# CD_Air_Detector_V2_0.net
KiCad netlist of a schematic drawn in EasyEDA Pro
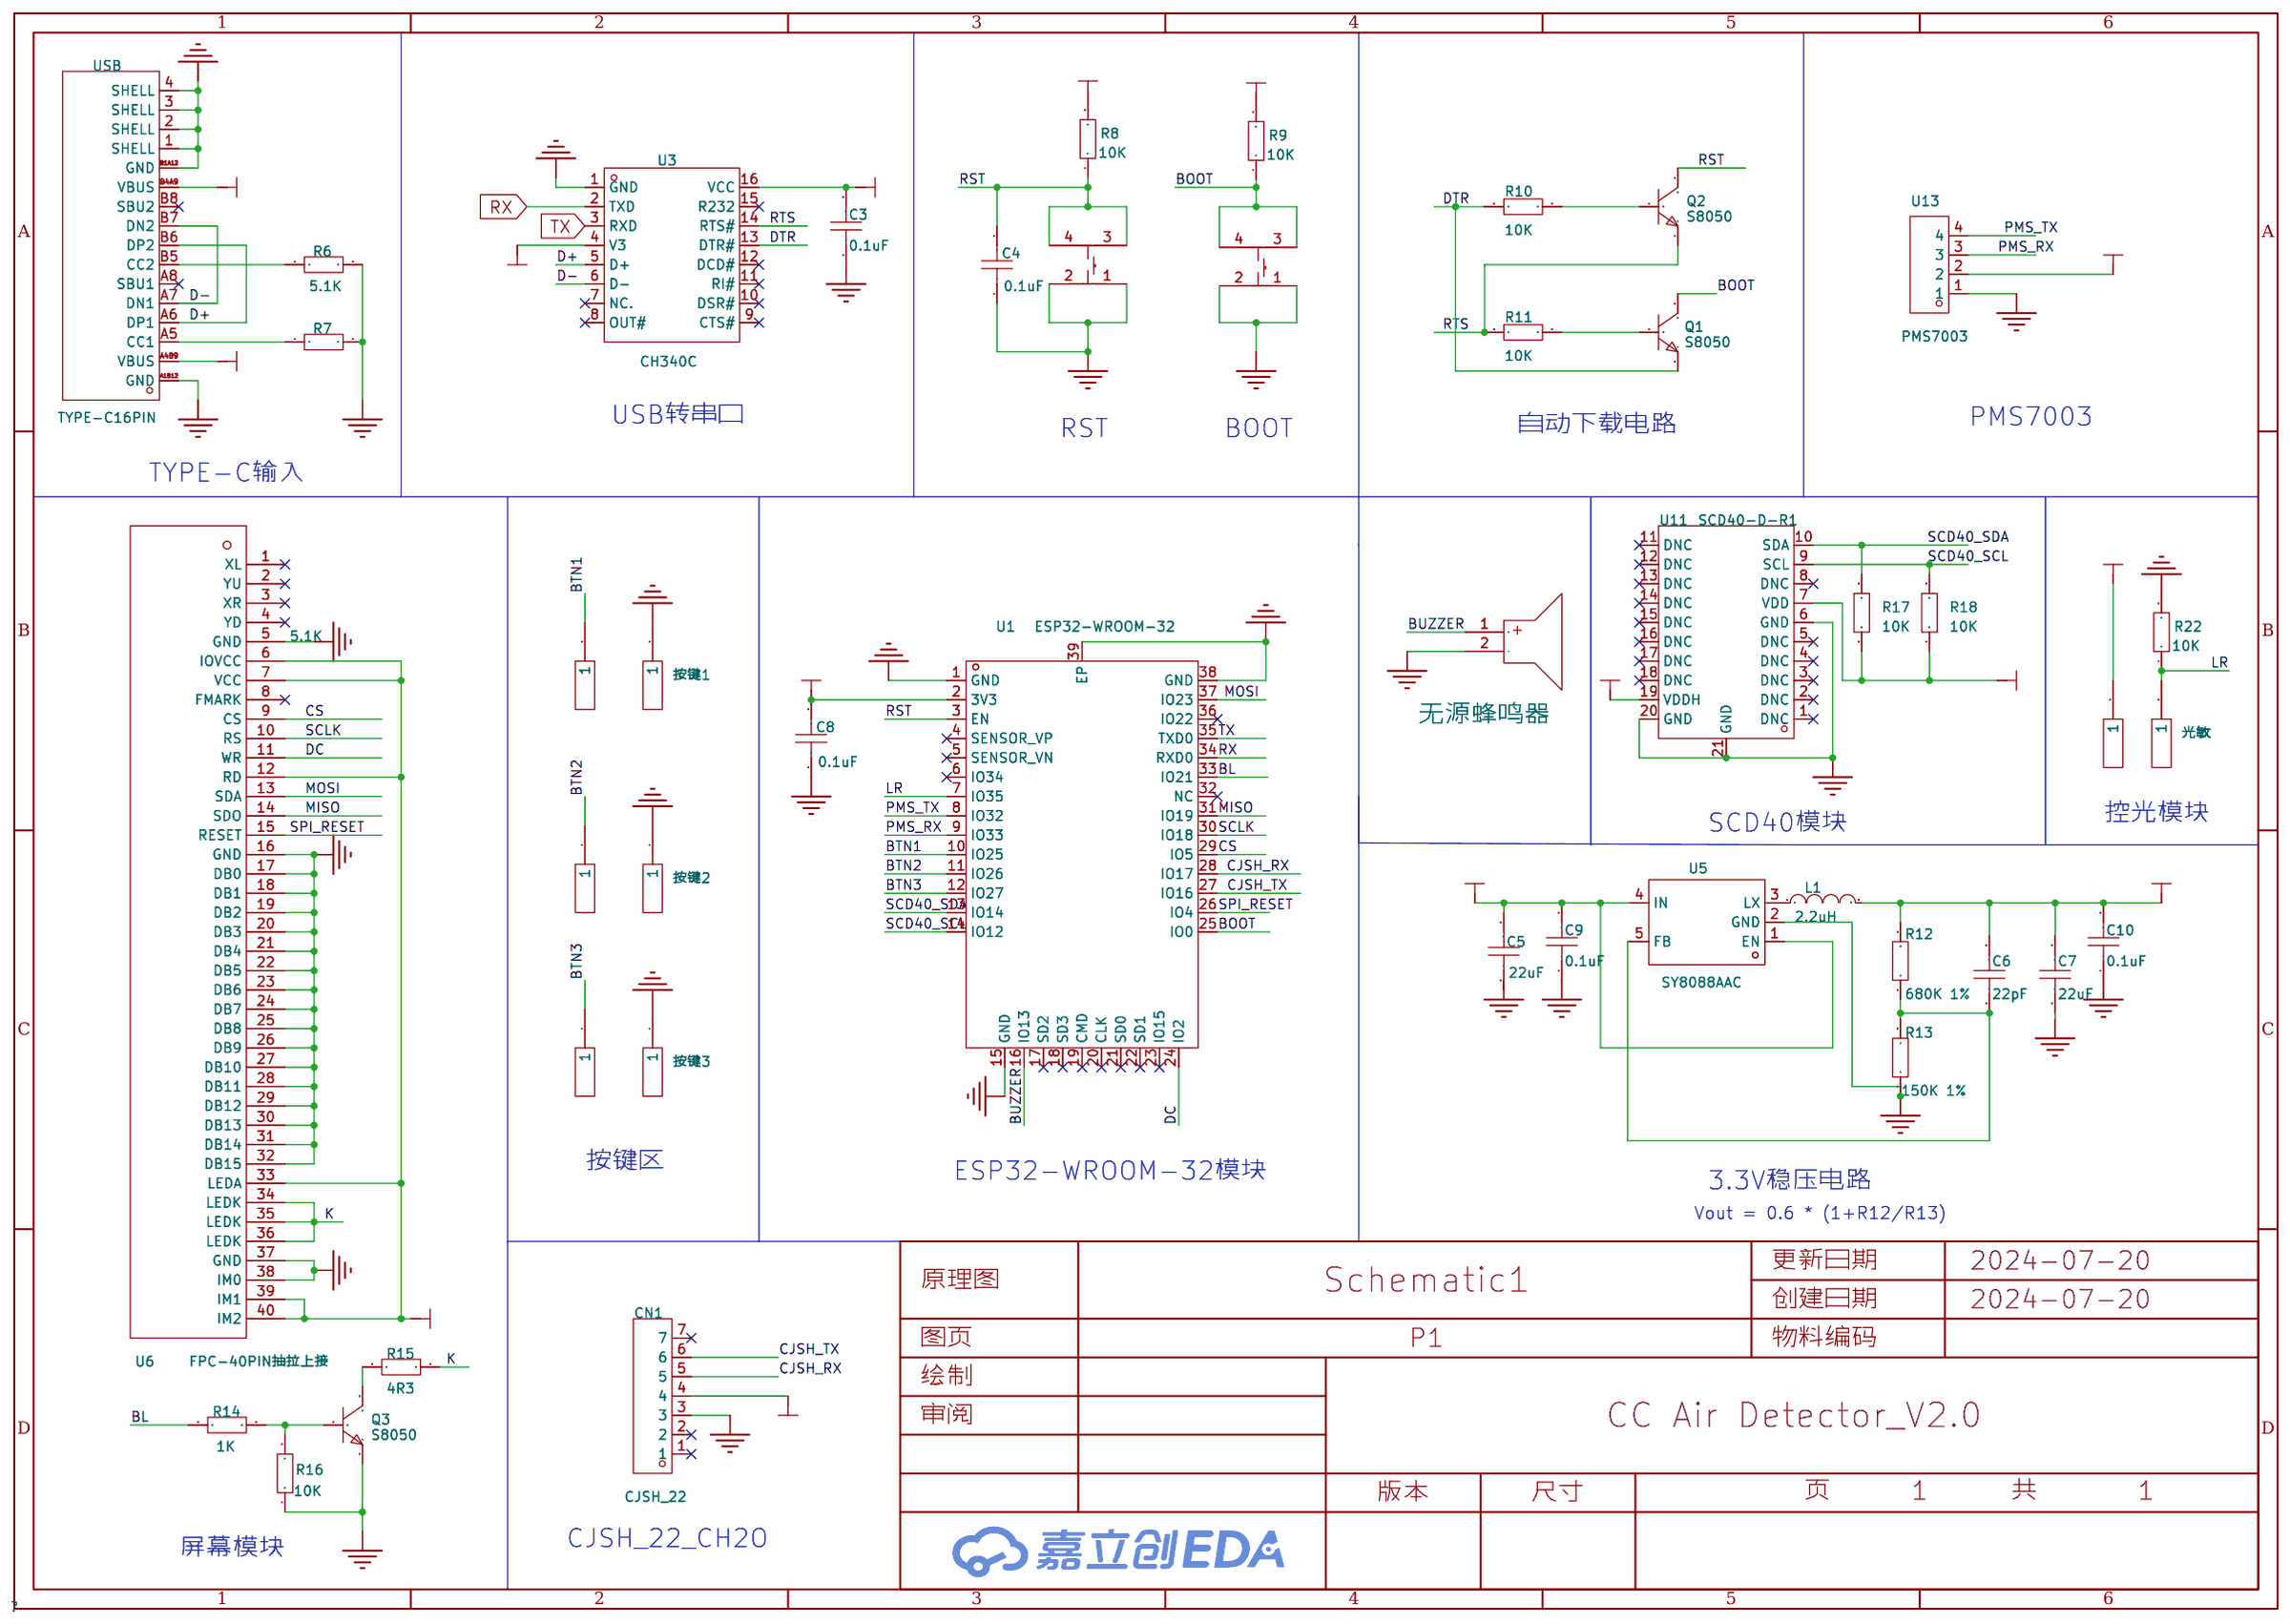
[diagram p0: schematic sheet]

(export (version "E")
  (design (tool "Eeschema 10.0.6"))
  (components
    (comp (ref "C3")
      (value "0.1uF")
      (footprint "easyedapro:C0603")
      (libsource (lib "easyedapro") (part "CapAcitance"))
    )
    (comp (ref "C4")
      (value "0.1uF")
      (footprint "easyedapro:C0603")
      (libsource (lib "easyedapro") (part "CapAcitance"))
    )
    (comp (ref "C5")
      (value "22uF")
      (footprint "easyedapro:C0603")
      (libsource (lib "easyedapro") (part "CapAcitance"))
    )
    (comp (ref "C6")
      (value "22pF")
      (footprint "easyedapro:C0603")
      (libsource (lib "easyedapro") (part "CapAcitance"))
    )
    (comp (ref "C7")
      (value "22uF")
      (footprint "easyedapro:C0603")
      (libsource (lib "easyedapro") (part "CapAcitance"))
    )
    (comp (ref "C8")
      (value "0.1uF")
      (footprint "easyedapro:C0603")
      (libsource (lib "easyedapro") (part "CapAcitance"))
    )
    (comp (ref "C9")
      (value "0.1uF")
      (footprint "easyedapro:C0603")
      (libsource (lib "easyedapro") (part "CapAcitance"))
    )
    (comp (ref "C10")
      (value "0.1uF")
      (footprint "easyedapro:C0603")
      (libsource (lib "easyedapro") (part "CapAcitance"))
    )
    (comp (ref "CN1")
      (value "CJSH_22")
      (footprint "easyedapro:CONN-TH_1.25T-7P-DP")
      (description "插针结构:1x7P;间距:1.25mm;安装方式:直插;参考系列:-;总PIN数:7P;排数:1;每排PIN数:7;行距:-;额定电流:1A;工作温度范围:-25°C~+85°C;")
      (fields (field (name "Manufacturer") "韩国韩荣"))
      (libsource (lib "easyedapro") (part "1.25T-7P-DP"))
    )
    (comp (ref "L1")
      (value "2.2uH")
      (footprint "easyedapro:L0805")
      (libsource (lib "easyedapro") (part "SDFL2012S100KTF"))
    )
    (comp (ref "Q1")
      (value "S8050")
      (footprint "easyedapro:SOT-23-3_L2.9-W1.3-P1.90-LS2.4-BR")
      (description "NPN 25V 500mA 120-400 SOT-23")
      (fields (field (name "Manufacturer") "Doeshare(德芯)"))
      (libsource (lib "easyedapro") (part "S8050_C2931719"))
    )
    (comp (ref "Q2")
      (value "S8050")
      (footprint "easyedapro:SOT-23-3_L2.9-W1.3-P1.90-LS2.4-BR")
      (description "NPN 25V 500mA 120-400 SOT-23")
      (fields (field (name "Manufacturer") "Doeshare(德芯)"))
      (libsource (lib "easyedapro") (part "S8050_C2931719"))
    )
    (comp (ref "Q3")
      (value "S8050")
      (footprint "easyedapro:SOT-23-3_L2.9-W1.3-P1.90-LS2.4-BR")
      (description "NPN 25V 500mA 120-400 SOT-23")
      (fields (field (name "Manufacturer") "Doeshare(德芯)"))
      (libsource (lib "easyedapro") (part "S8050_C2931719"))
    )
    (comp (ref "R6") (value "5.1K") (footprint "easyedapro:R0603") (libsource (lib "easyedapro") (part "电阻")))
    (comp (ref "R7") (value "5.1K") (footprint "easyedapro:R0603") (libsource (lib "easyedapro") (part "电阻")))
    (comp (ref "R8") (value "10K") (footprint "easyedapro:R0603") (libsource (lib "easyedapro") (part "电阻")))
    (comp (ref "R9") (value "10K") (footprint "easyedapro:R0603") (libsource (lib "easyedapro") (part "电阻")))
    (comp (ref "R10") (value "10K") (footprint "easyedapro:R0603") (libsource (lib "easyedapro") (part "电阻")))
    (comp (ref "R11") (value "10K") (footprint "easyedapro:R0603") (libsource (lib "easyedapro") (part "电阻")))
    (comp (ref "R12")
      (value "680K 1%")
      (footprint "easyedapro:R0603")
      (libsource (lib "easyedapro") (part "电阻"))
    )
    (comp (ref "R13")
      (value "150K 1%")
      (footprint "easyedapro:R0603")
      (libsource (lib "easyedapro") (part "电阻"))
    )
    (comp (ref "R14") (value "1K") (footprint "easyedapro:R0603") (libsource (lib "easyedapro") (part "电阻")))
    (comp (ref "R15") (value "4R3") (footprint "easyedapro:R0603") (libsource (lib "easyedapro") (part "电阻")))
    (comp (ref "R16") (value "10K") (footprint "easyedapro:R0603") (libsource (lib "easyedapro") (part "电阻")))
    (comp (ref "R17") (value "10K") (footprint "easyedapro:R0603") (libsource (lib "easyedapro") (part "电阻")))
    (comp (ref "R18") (value "10K") (footprint "easyedapro:R0603") (libsource (lib "easyedapro") (part "电阻")))
    (comp (ref "R22") (value "10K") (footprint "easyedapro:R0603") (libsource (lib "easyedapro") (part "电阻")))
    (comp (ref "U1")
      (value "ESP32-WROOM-32")
      (footprint "easyedapro:WIFIM-SMD_ESP-WROOM-32")
      (description "WiFi+双模蓝牙 双核CPU 网口 顶配MCU 低功耗蓝牙 ESP32系列ESP-WROOM-32模组/ESP-32S 4MB")
      (fields (field (name "Manufacturer") "ESPRESSIF(乐鑫)"))
      (libsource (lib "easyedapro") (part "ESP-WROOM-32"))
    )
    (comp (ref "U2")
      (value "贴片按键(轻触开关)")
      (footprint "easyedapro:SW-SMD_4P-L4.2-W3.2-P2.15-LS4.6")
      (libsource (lib "easyedapro") (part "贴片按键(轻触开关)"))
    )
    (comp (ref "U3")
      (value "CH340C")
      (footprint "easyedapro:SOP-16_L10.0-W3.9-P1.27-LS6.0-BL")
      (description "应用功能:收发器;接口协议:USB 2.0;数据速率:2Mbps;")
      (fields (field (name "Manufacturer") "WCH(南京沁恒)"))
      (libsource (lib "easyedapro") (part "CH340C"))
    )
    (comp (ref "U4")
      (value "贴片按键(轻触开关)")
      (footprint "easyedapro:SW-SMD_4P-L4.2-W3.2-P2.15-LS4.6")
      (libsource (lib "easyedapro") (part "贴片按键(轻触开关)"))
    )
    (comp (ref "U5")
      (value "SY8088AAC")
      (footprint "easyedapro:SOT-23-5_L3.0-W1.7-P0.95-LS2.8-BR")
      (description "功能类型:降压型;输入电压:-;输出电流(最大值):-;")
      (fields (field (name "Manufacturer") "silergy(矽力杰)"))
      (libsource (lib "easyedapro") (part "SY8088AAC"))
    )
    (comp (ref "U6")
      (value "FPC-40PIN抽拉上接")
      (footprint "easyedapro:FPC_40PIN")
      (libsource (lib "easyedapro") (part "FPC_连接器_40PIN"))
    )
    (comp (ref "U8")
      (value "~")
      (footprint "easyedapro:长圆形单面焊盘")
      (libsource (lib "easyedapro") (part "长圆形单面焊盘"))
    )
    (comp (ref "U9")
      (value "~")
      (footprint "easyedapro:长圆形单面焊盘")
      (libsource (lib "easyedapro") (part "长圆形单面焊盘"))
    )
    (comp (ref "U10")
      (value "~")
      (footprint "easyedapro:长圆形单面焊盘")
      (libsource (lib "easyedapro") (part "长圆形单面焊盘"))
    )
    (comp (ref "U11")
      (value "SCD40-D-R1")
      (footprint "easyedapro:LGA-20_L10.1-W10.1-P1.25-TL")
      (description "气体类型:空气质量;精度:±5%;")
      (fields (field (name "Manufacturer") "Sensirion(瑞士盛思锐)"))
      (libsource (lib "easyedapro") (part "SCD40-D-R1"))
    )
    (comp (ref "U12")
      (value "~")
      (footprint "easyedapro:长圆形单面焊盘")
      (libsource (lib "easyedapro") (part "长圆形单面焊盘"))
    )
    (comp (ref "U13")
      (value "PMS7003")
      (footprint "easyedapro:CONN-TH_4P-P2.50-XH2.54-4P")
      (libsource (lib "easyedapro") (part "XH2.54-4P(直针)"))
    )
    (comp (ref "USB")
      (value "TYPE-C16PIN")
      (footprint "easyedapro:USB-C-SMD_TYPE-C16PIN")
      (description "连接器类型:Type-C;标准:-;公母:母;端口数量:1;触点数量:16P;安装方式:卧贴;额定电流 - 电源:3A;工作温度范围:-40°C~+85°C;")
      (fields (field (name "Manufacturer") "SHOU HAN(首韩)"))
      (libsource (lib "easyedapro") (part "TYPE-C16PIN"))
    )
    (comp (ref "光敏")
      (value "~")
      (footprint "easyedapro:长圆形单面焊盘")
      (libsource (lib "easyedapro") (part "长圆形单面焊盘"))
    )
    (comp (ref "按键1")
      (value "~")
      (footprint "easyedapro:长圆形单面焊盘")
      (libsource (lib "easyedapro") (part "长圆形单面焊盘"))
    )
    (comp (ref "按键2")
      (value "~")
      (footprint "easyedapro:长圆形单面焊盘")
      (libsource (lib "easyedapro") (part "长圆形单面焊盘"))
    )
    (comp (ref "按键3")
      (value "~")
      (footprint "easyedapro:长圆形单面焊盘")
      (libsource (lib "easyedapro") (part "长圆形单面焊盘"))
    )
    (comp (ref "无源蜂鸣器")
      (value "无源蜂鸣器")
      (footprint "easyedapro:BUZ-TH_BD12.0-P6.50-D0.6-FD")
      (fields (field (name "Manufacturer") "Fengming(锋鸣电子)"))
      (libsource (lib "easyedapro") (part "YS-MBZ12095C05R42K4000"))
    )
  )
  (nets
    (net (code "1") (name "/BL") (class "Default")
      (node (ref "R14") (pin "1") (pinfunction "1_1") (pintype "input"))
      (node (ref "U1") (pin "33") (pinfunction "IO21_33") (pintype "unspecified"))
    )
    (net (code "2") (name "/BOOT") (class "Default")
      (node (ref "Q1") (pin "3") (pinfunction "C_3") (pintype "input"))
      (node (ref "R9") (pin "1") (pinfunction "1_1") (pintype "input"))
      (node (ref "U1") (pin "25") (pinfunction "IO0_25") (pintype "unspecified"))
      (node (ref "U4") (pin "3") (pinfunction "3_3") (pintype "unspecified"))
      (node (ref "U4") (pin "4") (pinfunction "4_4") (pintype "unspecified"))
    )
    (net (code "3") (name "/BTN1") (class "Default")
      (node (ref "U1") (pin "10") (pinfunction "IO25_10") (pintype "unspecified"))
      (node (ref "U8") (pin "1") (pinfunction "1_1") (pintype "input"))
    )
    (net (code "4") (name "/BTN2") (class "Default")
      (node (ref "U1") (pin "11") (pinfunction "IO26_11") (pintype "unspecified"))
      (node (ref "U9") (pin "1") (pinfunction "1_1") (pintype "input"))
    )
    (net (code "5") (name "/BTN3") (class "Default")
      (node (ref "U1") (pin "12") (pinfunction "IO27_12") (pintype "unspecified"))
      (node (ref "U10") (pin "1") (pinfunction "1_1") (pintype "input"))
    )
    (net (code "6") (name "/BUZZER") (class "Default")
      (node (ref "U1") (pin "16") (pinfunction "IO13_16") (pintype "unspecified"))
      (node (ref "无源蜂鸣器") (pin "1") (pinfunction "+_1") (pintype "input"))
    )
    (net (code "7") (name "/CJSH_RX") (class "Default")
      (node (ref "CN1") (pin "5") (pinfunction "5_5") (pintype "unspecified"))
      (node (ref "U1") (pin "28") (pinfunction "IO17_28") (pintype "unspecified"))
    )
    (net (code "8") (name "/CJSH_TX") (class "Default")
      (node (ref "CN1") (pin "6") (pinfunction "6_6") (pintype "unspecified"))
      (node (ref "U1") (pin "27") (pinfunction "IO16_27") (pintype "unspecified"))
    )
    (net (code "9") (name "/CS") (class "Default")
      (node (ref "U1") (pin "29") (pinfunction "IO5_29") (pintype "unspecified"))
      (node (ref "U6") (pin "9") (pinfunction "CS_9") (pintype "input"))
    )
    (net (code "10") (name "/D+") (class "Default")
      (node (ref "U3") (pin "5") (pinfunction "D+_5") (pintype "unspecified"))
      (node (ref "USB") (pin "A6") (pinfunction "DP1_A6") (pintype "unspecified"))
      (node (ref "USB") (pin "B6") (pinfunction "DP2_B6") (pintype "unspecified"))
    )
    (net (code "11") (name "/D-") (class "Default")
      (node (ref "U3") (pin "6") (pinfunction "D-_6") (pintype "unspecified"))
      (node (ref "USB") (pin "A7") (pinfunction "DN1_A7") (pintype "unspecified"))
      (node (ref "USB") (pin "B7") (pinfunction "DN2_B7") (pintype "unspecified"))
    )
    (net (code "12") (name "/DC") (class "Default")
      (node (ref "U1") (pin "24") (pinfunction "IO2_24") (pintype "unspecified"))
      (node (ref "U6") (pin "11") (pinfunction "WR_11") (pintype "input"))
    )
    (net (code "13") (name "/DTR") (class "Default")
      (node (ref "Q1") (pin "2") (pinfunction "E_2") (pintype "input"))
      (node (ref "R10") (pin "1") (pinfunction "1_1") (pintype "input"))
      (node (ref "U3") (pin "13") (pinfunction "DTR#_13") (pintype "unspecified"))
    )
    (net (code "14") (name "/K") (class "Default")
      (node (ref "R15") (pin "2") (pinfunction "2_2") (pintype "input"))
      (node (ref "U6") (pin "34") (pinfunction "LEDK_34") (pintype "input"))
      (node (ref "U6") (pin "35") (pinfunction "LEDK_35") (pintype "input"))
      (node (ref "U6") (pin "36") (pinfunction "LEDK_36") (pintype "input"))
    )
    (net (code "15") (name "/LR") (class "Default")
      (node (ref "R22") (pin "1") (pinfunction "1_1") (pintype "input"))
      (node (ref "U1") (pin "7") (pinfunction "IO35_7") (pintype "unspecified"))
      (node (ref "光敏") (pin "1") (pinfunction "1_1") (pintype "input"))
    )
    (net (code "16") (name "/MISO") (class "Default")
      (node (ref "U1") (pin "31") (pinfunction "IO19_31") (pintype "unspecified"))
      (node (ref "U6") (pin "14") (pinfunction "SDO_14") (pintype "input"))
    )
    (net (code "17") (name "/MOSI") (class "Default")
      (node (ref "U1") (pin "37") (pinfunction "IO23_37") (pintype "unspecified"))
      (node (ref "U6") (pin "13") (pinfunction "SDA_13") (pintype "input"))
    )
    (net (code "18") (name "/PMS_RX") (class "Default")
      (node (ref "U1") (pin "9") (pinfunction "IO33_9") (pintype "unspecified"))
      (node (ref "U13") (pin "3") (pinfunction "3_3") (pintype "unspecified"))
    )
    (net (code "19") (name "/PMS_TX") (class "Default")
      (node (ref "U1") (pin "8") (pinfunction "IO32_8") (pintype "unspecified"))
      (node (ref "U13") (pin "4") (pinfunction "4_4") (pintype "unspecified"))
    )
    (net (code "20") (name "/RST") (class "Default")
      (node (ref "C4") (pin "2") (pinfunction "2_2") (pintype "input"))
      (node (ref "Q2") (pin "3") (pinfunction "C_3") (pintype "input"))
      (node (ref "R8") (pin "1") (pinfunction "1_1") (pintype "input"))
      (node (ref "U1") (pin "3") (pinfunction "EN_3") (pintype "unspecified"))
      (node (ref "U2") (pin "3") (pinfunction "3_3") (pintype "unspecified"))
      (node (ref "U2") (pin "4") (pinfunction "4_4") (pintype "unspecified"))
    )
    (net (code "21") (name "/RTS") (class "Default")
      (node (ref "Q2") (pin "2") (pinfunction "E_2") (pintype "input"))
      (node (ref "R11") (pin "1") (pinfunction "1_1") (pintype "input"))
      (node (ref "U3") (pin "14") (pinfunction "RTS#_14") (pintype "unspecified"))
    )
    (net (code "22") (name "/SCD40_SCL") (class "Default")
      (node (ref "R18") (pin "2") (pinfunction "2_2") (pintype "input"))
      (node (ref "U1") (pin "14") (pinfunction "IO12_14") (pintype "unspecified"))
      (node (ref "U11") (pin "9") (pinfunction "SCL_9") (pintype "unspecified"))
    )
    (net (code "23") (name "/SCD40_SDA") (class "Default")
      (node (ref "R17") (pin "2") (pinfunction "2_2") (pintype "input"))
      (node (ref "U1") (pin "13") (pinfunction "IO14_13") (pintype "unspecified"))
      (node (ref "U11") (pin "10") (pinfunction "SDA_10") (pintype "unspecified"))
    )
    (net (code "24") (name "/SCLK") (class "Default")
      (node (ref "U1") (pin "30") (pinfunction "IO18_30") (pintype "unspecified"))
      (node (ref "U6") (pin "10") (pinfunction "RS_10") (pintype "input"))
    )
    (net (code "25") (name "/SPI_RESET") (class "Default")
      (node (ref "U1") (pin "26") (pinfunction "IO4_26") (pintype "unspecified"))
      (node (ref "U6") (pin "15") (pinfunction "RESET_15") (pintype "input"))
    )
    (net (code "26") (name "3V3") (class "Default")
      (node (ref "C10") (pin "2") (pinfunction "2_2") (pintype "input"))
      (node (ref "C3") (pin "2") (pinfunction "2_2") (pintype "input"))
      (node (ref "C6") (pin "2") (pinfunction "2_2") (pintype "input"))
      (node (ref "C7") (pin "2") (pinfunction "2_2") (pintype "input"))
      (node (ref "C8") (pin "2") (pinfunction "2_2") (pintype "input"))
      (node (ref "L1") (pin "2") (pinfunction "2_2") (pintype "unspecified"))
      (node (ref "R12") (pin "2") (pinfunction "2_2") (pintype "input"))
      (node (ref "R17") (pin "1") (pinfunction "1_1") (pintype "input"))
      (node (ref "R18") (pin "1") (pinfunction "1_1") (pintype "input"))
      (node (ref "R8") (pin "2") (pinfunction "2_2") (pintype "input"))
      (node (ref "R9") (pin "2") (pinfunction "2_2") (pintype "input"))
      (node (ref "U1") (pin "2") (pinfunction "3V3_2") (pintype "unspecified"))
      (node (ref "U11") (pin "19") (pinfunction "VDDH_19") (pintype "unspecified"))
      (node (ref "U11") (pin "7") (pinfunction "VDD_7") (pintype "unspecified"))
      (node (ref "U12") (pin "1") (pinfunction "1_1") (pintype "input"))
      (node (ref "U3") (pin "16") (pinfunction "VCC_16") (pintype "unspecified"))
      (node (ref "U3") (pin "4") (pinfunction "V3_4") (pintype "unspecified"))
      (node (ref "U6") (pin "12") (pinfunction "RD_12") (pintype "input"))
      (node (ref "U6") (pin "33") (pinfunction "LEDA_33") (pintype "input"))
      (node (ref "U6") (pin "39") (pinfunction "IM1_39") (pintype "input"))
      (node (ref "U6") (pin "40") (pinfunction "IM2_40") (pintype "input"))
      (node (ref "U6") (pin "6") (pinfunction "IOVCC_6") (pintype "input"))
      (node (ref "U6") (pin "7") (pinfunction "VCC_7") (pintype "input"))
    )
    (net (code "27") (name "GND") (class "Default")
      (node (ref "C10") (pin "1") (pinfunction "1_1") (pintype "input"))
      (node (ref "C3") (pin "1") (pinfunction "1_1") (pintype "input"))
      (node (ref "C4") (pin "1") (pinfunction "1_1") (pintype "input"))
      (node (ref "C5") (pin "1") (pinfunction "1_1") (pintype "input"))
      (node (ref "C7") (pin "1") (pinfunction "1_1") (pintype "input"))
      (node (ref "C8") (pin "1") (pinfunction "1_1") (pintype "input"))
      (node (ref "C9") (pin "1") (pinfunction "1_1") (pintype "input"))
      (node (ref "CN1") (pin "3") (pinfunction "3_3") (pintype "unspecified"))
      (node (ref "Q3") (pin "2") (pinfunction "E_2") (pintype "input"))
      (node (ref "R13") (pin "1") (pinfunction "1_1") (pintype "input"))
      (node (ref "R16") (pin "1") (pinfunction "1_1") (pintype "input"))
      (node (ref "R22") (pin "2") (pinfunction "2_2") (pintype "input"))
      (node (ref "R6") (pin "2") (pinfunction "2_2") (pintype "input"))
      (node (ref "R7") (pin "2") (pinfunction "2_2") (pintype "input"))
      (node (ref "U1") (pin "1") (pinfunction "GND_1") (pintype "unspecified"))
      (node (ref "U1") (pin "15") (pinfunction "GND_15") (pintype "unspecified"))
      (node (ref "U1") (pin "38") (pinfunction "GND_38") (pintype "unspecified"))
      (node (ref "U1") (pin "39") (pinfunction "EP_39") (pintype "unspecified"))
      (node (ref "U11") (pin "20") (pinfunction "GND_20") (pintype "unspecified"))
      (node (ref "U11") (pin "21") (pinfunction "GND_21") (pintype "unspecified"))
      (node (ref "U11") (pin "6") (pinfunction "GND_6") (pintype "unspecified"))
      (node (ref "U13") (pin "1") (pinfunction "1_1") (pintype "unspecified"))
      (node (ref "U2") (pin "1") (pinfunction "1_1") (pintype "unspecified"))
      (node (ref "U2") (pin "2") (pinfunction "2_2") (pintype "unspecified"))
      (node (ref "U3") (pin "1") (pinfunction "GND_1") (pintype "unspecified"))
      (node (ref "U4") (pin "1") (pinfunction "1_1") (pintype "unspecified"))
      (node (ref "U4") (pin "2") (pinfunction "2_2") (pintype "unspecified"))
      (node (ref "U5") (pin "2") (pinfunction "GND_2") (pintype "input"))
      (node (ref "U6") (pin "16") (pinfunction "GND_16") (pintype "input"))
      (node (ref "U6") (pin "17") (pinfunction "DB0_17") (pintype "input"))
      (node (ref "U6") (pin "18") (pinfunction "DB1_18") (pintype "input"))
      (node (ref "U6") (pin "19") (pinfunction "DB2_19") (pintype "input"))
      (node (ref "U6") (pin "20") (pinfunction "DB3_20") (pintype "input"))
      (node (ref "U6") (pin "21") (pinfunction "DB4_21") (pintype "input"))
      (node (ref "U6") (pin "22") (pinfunction "DB5_22") (pintype "input"))
      (node (ref "U6") (pin "23") (pinfunction "DB6_23") (pintype "input"))
      (node (ref "U6") (pin "24") (pinfunction "DB7_24") (pintype "input"))
      (node (ref "U6") (pin "25") (pinfunction "DB8_25") (pintype "input"))
      (node (ref "U6") (pin "26") (pinfunction "DB9_26") (pintype "input"))
      (node (ref "U6") (pin "27") (pinfunction "DB10_27") (pintype "input"))
      (node (ref "U6") (pin "28") (pinfunction "DB11_28") (pintype "input"))
      (node (ref "U6") (pin "29") (pinfunction "DB12_29") (pintype "input"))
      (node (ref "U6") (pin "30") (pinfunction "DB13_30") (pintype "input"))
      (node (ref "U6") (pin "31") (pinfunction "DB14_31") (pintype "input"))
      (node (ref "U6") (pin "32") (pinfunction "DB15_32") (pintype "input"))
      (node (ref "U6") (pin "37") (pinfunction "GND_37") (pintype "input"))
      (node (ref "U6") (pin "38") (pinfunction "IM0_38") (pintype "input"))
      (node (ref "U6") (pin "5") (pinfunction "GND_5") (pintype "input"))
      (node (ref "USB") (pin "1") (pinfunction "SHELL_1") (pintype "unspecified"))
      (node (ref "USB") (pin "2") (pinfunction "SHELL_2") (pintype "unspecified"))
      (node (ref "USB") (pin "3") (pinfunction "SHELL_3") (pintype "unspecified"))
      (node (ref "USB") (pin "4") (pinfunction "SHELL_4") (pintype "unspecified"))
      (node (ref "USB") (pin "A1B12") (pinfunction "GND_A1B12") (pintype "unspecified"))
      (node (ref "USB") (pin "B1A12") (pinfunction "GND_B1A12") (pintype "unspecified"))
      (node (ref "按键1") (pin "1") (pinfunction "1_1") (pintype "input"))
      (node (ref "按键2") (pin "1") (pinfunction "1_1") (pintype "input"))
      (node (ref "按键3") (pin "1") (pinfunction "1_1") (pintype "input"))
      (node (ref "无源蜂鸣器") (pin "2") (pinfunction "-_2") (pintype "input"))
    )
    (net (code "28") (name "Net-(Q1-B)") (class "Default")
      (node (ref "Q1") (pin "1") (pinfunction "B_1") (pintype "input"))
      (node (ref "R11") (pin "2") (pinfunction "2_2") (pintype "input"))
    )
    (net (code "29") (name "Net-(Q2-B)") (class "Default")
      (node (ref "Q2") (pin "1") (pinfunction "B_1") (pintype "input"))
      (node (ref "R10") (pin "2") (pinfunction "2_2") (pintype "input"))
    )
    (net (code "30") (name "Net-(Q3-B)") (class "Default")
      (node (ref "Q3") (pin "1") (pinfunction "B_1") (pintype "input"))
      (node (ref "R14") (pin "2") (pinfunction "2_2") (pintype "input"))
      (node (ref "R16") (pin "2") (pinfunction "2_2") (pintype "input"))
    )
    (net (code "31") (name "Net-(Q3-C)") (class "Default")
      (node (ref "Q3") (pin "3") (pinfunction "C_3") (pintype "input"))
      (node (ref "R15") (pin "1") (pinfunction "1_1") (pintype "input"))
    )
    (net (code "32") (name "Net-(U5-FB)") (class "Default")
      (node (ref "C6") (pin "1") (pinfunction "1_1") (pintype "input"))
      (node (ref "R12") (pin "1") (pinfunction "1_1") (pintype "input"))
      (node (ref "R13") (pin "2") (pinfunction "2_2") (pintype "input"))
      (node (ref "U5") (pin "5") (pinfunction "FB_5") (pintype "input"))
    )
    (net (code "33") (name "Net-(U5-LX)") (class "Default")
      (node (ref "L1") (pin "1") (pinfunction "1_1") (pintype "unspecified"))
      (node (ref "U5") (pin "3") (pinfunction "LX_3") (pintype "input"))
    )
    (net (code "34") (name "Net-(USB-CC1)") (class "Default")
      (node (ref "R7") (pin "1") (pinfunction "1_1") (pintype "input"))
      (node (ref "USB") (pin "A5") (pinfunction "CC1_A5") (pintype "unspecified"))
    )
    (net (code "35") (name "Net-(USB-CC2)") (class "Default")
      (node (ref "R6") (pin "1") (pinfunction "1_1") (pintype "input"))
      (node (ref "USB") (pin "B5") (pinfunction "CC2_B5") (pintype "unspecified"))
    )
    (net (code "36") (name "RX") (class "Default")
      (node (ref "U1") (pin "34") (pinfunction "RXD0_34") (pintype "unspecified"))
      (node (ref "U3") (pin "2") (pinfunction "TXD_2") (pintype "unspecified"))
    )
    (net (code "37") (name "TX") (class "Default")
      (node (ref "U1") (pin "35") (pinfunction "TXD0_35") (pintype "unspecified"))
      (node (ref "U3") (pin "3") (pinfunction "RXD_3") (pintype "unspecified"))
    )
    (net (code "38") (name "VBUS") (class "Default")
      (node (ref "C5") (pin "2") (pinfunction "2_2") (pintype "input"))
      (node (ref "C9") (pin "2") (pinfunction "2_2") (pintype "input"))
      (node (ref "CN1") (pin "4") (pinfunction "4_4") (pintype "unspecified"))
      (node (ref "U13") (pin "2") (pinfunction "2_2") (pintype "unspecified"))
      (node (ref "U5") (pin "1") (pinfunction "EN_1") (pintype "input"))
      (node (ref "U5") (pin "4") (pinfunction "IN_4") (pintype "input"))
      (node (ref "USB") (pin "A4B9") (pinfunction "VBUS_A4B9") (pintype "unspecified"))
      (node (ref "USB") (pin "B4A9") (pinfunction "VBUS_B4A9") (pintype "unspecified"))
    )
    (net (code "39") (name "unconnected-(CN1-Pad1)") (class "Default")
      (node (ref "CN1") (pin "1") (pinfunction "1_1") (pintype "unspecified+no_connect"))
    )
    (net (code "40") (name "unconnected-(CN1-Pad2)") (class "Default")
      (node (ref "CN1") (pin "2") (pinfunction "2_2") (pintype "unspecified+no_connect"))
    )
    (net (code "41") (name "unconnected-(CN1-Pad7)") (class "Default")
      (node (ref "CN1") (pin "7") (pinfunction "7_7") (pintype "unspecified+no_connect"))
    )
    (net (code "42") (name "unconnected-(U1-CLK-Pad20)") (class "Default")
      (node (ref "U1") (pin "20") (pinfunction "CLK_20") (pintype "unspecified+no_connect"))
    )
    (net (code "43") (name "unconnected-(U1-CMD-Pad19)") (class "Default")
      (node (ref "U1") (pin "19") (pinfunction "CMD_19") (pintype "unspecified+no_connect"))
    )
    (net (code "44") (name "unconnected-(U1-IO15-Pad23)") (class "Default")
      (node (ref "U1") (pin "23") (pinfunction "IO15_23") (pintype "unspecified+no_connect"))
    )
    (net (code "45") (name "unconnected-(U1-IO22-Pad36)") (class "Default")
      (node (ref "U1") (pin "36") (pinfunction "IO22_36") (pintype "unspecified+no_connect"))
    )
    (net (code "46") (name "unconnected-(U1-IO34-Pad6)") (class "Default")
      (node (ref "U1") (pin "6") (pinfunction "IO34_6") (pintype "unspecified+no_connect"))
    )
    (net (code "47") (name "unconnected-(U1-NC-Pad32)") (class "Default")
      (node (ref "U1") (pin "32") (pinfunction "NC_32") (pintype "unspecified+no_connect"))
    )
    (net (code "48") (name "unconnected-(U1-SD0-Pad21)") (class "Default")
      (node (ref "U1") (pin "21") (pinfunction "SD0_21") (pintype "unspecified+no_connect"))
    )
    (net (code "49") (name "unconnected-(U1-SD1-Pad22)") (class "Default")
      (node (ref "U1") (pin "22") (pinfunction "SD1_22") (pintype "unspecified+no_connect"))
    )
    (net (code "50") (name "unconnected-(U1-SD2-Pad17)") (class "Default")
      (node (ref "U1") (pin "17") (pinfunction "SD2_17") (pintype "unspecified+no_connect"))
    )
    (net (code "51") (name "unconnected-(U1-SD3-Pad18)") (class "Default")
      (node (ref "U1") (pin "18") (pinfunction "SD3_18") (pintype "unspecified+no_connect"))
    )
    (net (code "52") (name "unconnected-(U1-SENSOR_VN-Pad5)") (class "Default")
      (node (ref "U1") (pin "5") (pinfunction "SENSOR_VN_5") (pintype "unspecified+no_connect"))
    )
    (net (code "53") (name "unconnected-(U1-SENSOR_VP-Pad4)") (class "Default")
      (node (ref "U1") (pin "4") (pinfunction "SENSOR_VP_4") (pintype "unspecified+no_connect"))
    )
    (net (code "54") (name "unconnected-(U3-CTS#-Pad9)") (class "Default")
      (node (ref "U3") (pin "9") (pinfunction "CTS#_9") (pintype "unspecified+no_connect"))
    )
    (net (code "55") (name "unconnected-(U3-DCD#-Pad12)") (class "Default")
      (node (ref "U3") (pin "12") (pinfunction "DCD#_12") (pintype "unspecified+no_connect"))
    )
    (net (code "56") (name "unconnected-(U3-DSR#-Pad10)") (class "Default")
      (node (ref "U3") (pin "10") (pinfunction "DSR#_10") (pintype "unspecified+no_connect"))
    )
    (net (code "57") (name "unconnected-(U3-NC.-Pad7)") (class "Default")
      (node (ref "U3") (pin "7") (pinfunction "NC._7") (pintype "unspecified+no_connect"))
    )
    (net (code "58") (name "unconnected-(U3-OUT#-Pad8)") (class "Default")
      (node (ref "U3") (pin "8") (pinfunction "OUT#_8") (pintype "unspecified+no_connect"))
    )
    (net (code "59") (name "unconnected-(U3-R232-Pad15)") (class "Default")
      (node (ref "U3") (pin "15") (pinfunction "R232_15") (pintype "unspecified+no_connect"))
    )
    (net (code "60") (name "unconnected-(U3-RI#-Pad11)") (class "Default")
      (node (ref "U3") (pin "11") (pinfunction "RI#_11") (pintype "unspecified+no_connect"))
    )
    (net (code "61") (name "unconnected-(U6-FMARK-Pad8)") (class "Default")
      (node (ref "U6") (pin "8") (pinfunction "FMARK_8") (pintype "input+no_connect"))
    )
    (net (code "62") (name "unconnected-(U6-XL-Pad1)") (class "Default")
      (node (ref "U6") (pin "1") (pinfunction "XL_1") (pintype "input+no_connect"))
    )
    (net (code "63") (name "unconnected-(U6-XR-Pad3)") (class "Default")
      (node (ref "U6") (pin "3") (pinfunction "XR_3") (pintype "input+no_connect"))
    )
    (net (code "64") (name "unconnected-(U6-YD-Pad4)") (class "Default")
      (node (ref "U6") (pin "4") (pinfunction "YD_4") (pintype "input+no_connect"))
    )
    (net (code "65") (name "unconnected-(U6-YU-Pad2)") (class "Default")
      (node (ref "U6") (pin "2") (pinfunction "YU_2") (pintype "input+no_connect"))
    )
    (net (code "66") (name "unconnected-(U11-DNC-Pad1)") (class "Default")
      (node (ref "U11") (pin "1") (pinfunction "DNC_1") (pintype "unspecified+no_connect"))
    )
    (net (code "67") (name "unconnected-(U11-DNC-Pad2)") (class "Default")
      (node (ref "U11") (pin "2") (pinfunction "DNC_2") (pintype "unspecified+no_connect"))
    )
    (net (code "68") (name "unconnected-(U11-DNC-Pad3)") (class "Default")
      (node (ref "U11") (pin "3") (pinfunction "DNC_3") (pintype "unspecified+no_connect"))
    )
    (net (code "69") (name "unconnected-(U11-DNC-Pad4)") (class "Default")
      (node (ref "U11") (pin "4") (pinfunction "DNC_4") (pintype "unspecified+no_connect"))
    )
    (net (code "70") (name "unconnected-(U11-DNC-Pad5)") (class "Default")
      (node (ref "U11") (pin "5") (pinfunction "DNC_5") (pintype "unspecified+no_connect"))
    )
    (net (code "71") (name "unconnected-(U11-DNC-Pad8)") (class "Default")
      (node (ref "U11") (pin "8") (pinfunction "DNC_8") (pintype "unspecified+no_connect"))
    )
    (net (code "72") (name "unconnected-(U11-DNC-Pad11)") (class "Default")
      (node (ref "U11") (pin "11") (pinfunction "DNC_11") (pintype "unspecified+no_connect"))
    )
    (net (code "73") (name "unconnected-(U11-DNC-Pad12)") (class "Default")
      (node (ref "U11") (pin "12") (pinfunction "DNC_12") (pintype "unspecified+no_connect"))
    )
    (net (code "74") (name "unconnected-(U11-DNC-Pad13)") (class "Default")
      (node (ref "U11") (pin "13") (pinfunction "DNC_13") (pintype "unspecified+no_connect"))
    )
    (net (code "75") (name "unconnected-(U11-DNC-Pad14)") (class "Default")
      (node (ref "U11") (pin "14") (pinfunction "DNC_14") (pintype "unspecified+no_connect"))
    )
    (net (code "76") (name "unconnected-(U11-DNC-Pad15)") (class "Default")
      (node (ref "U11") (pin "15") (pinfunction "DNC_15") (pintype "unspecified+no_connect"))
    )
    (net (code "77") (name "unconnected-(U11-DNC-Pad16)") (class "Default")
      (node (ref "U11") (pin "16") (pinfunction "DNC_16") (pintype "unspecified+no_connect"))
    )
    (net (code "78") (name "unconnected-(U11-DNC-Pad17)") (class "Default")
      (node (ref "U11") (pin "17") (pinfunction "DNC_17") (pintype "unspecified+no_connect"))
    )
    (net (code "79") (name "unconnected-(U11-DNC-Pad18)") (class "Default")
      (node (ref "U11") (pin "18") (pinfunction "DNC_18") (pintype "unspecified+no_connect"))
    )
    (net (code "80") (name "unconnected-(USB-SBU1-PadA8)") (class "Default")
      (node (ref "USB") (pin "A8") (pinfunction "SBU1_A8") (pintype "unspecified+no_connect"))
    )
    (net (code "81") (name "unconnected-(USB-SBU2-PadB8)") (class "Default")
      (node (ref "USB") (pin "B8") (pinfunction "SBU2_B8") (pintype "unspecified+no_connect"))
    )
  )
)
